# usb_to_uart.net
KiCad netlist of a schematic drawn in Altium Designer
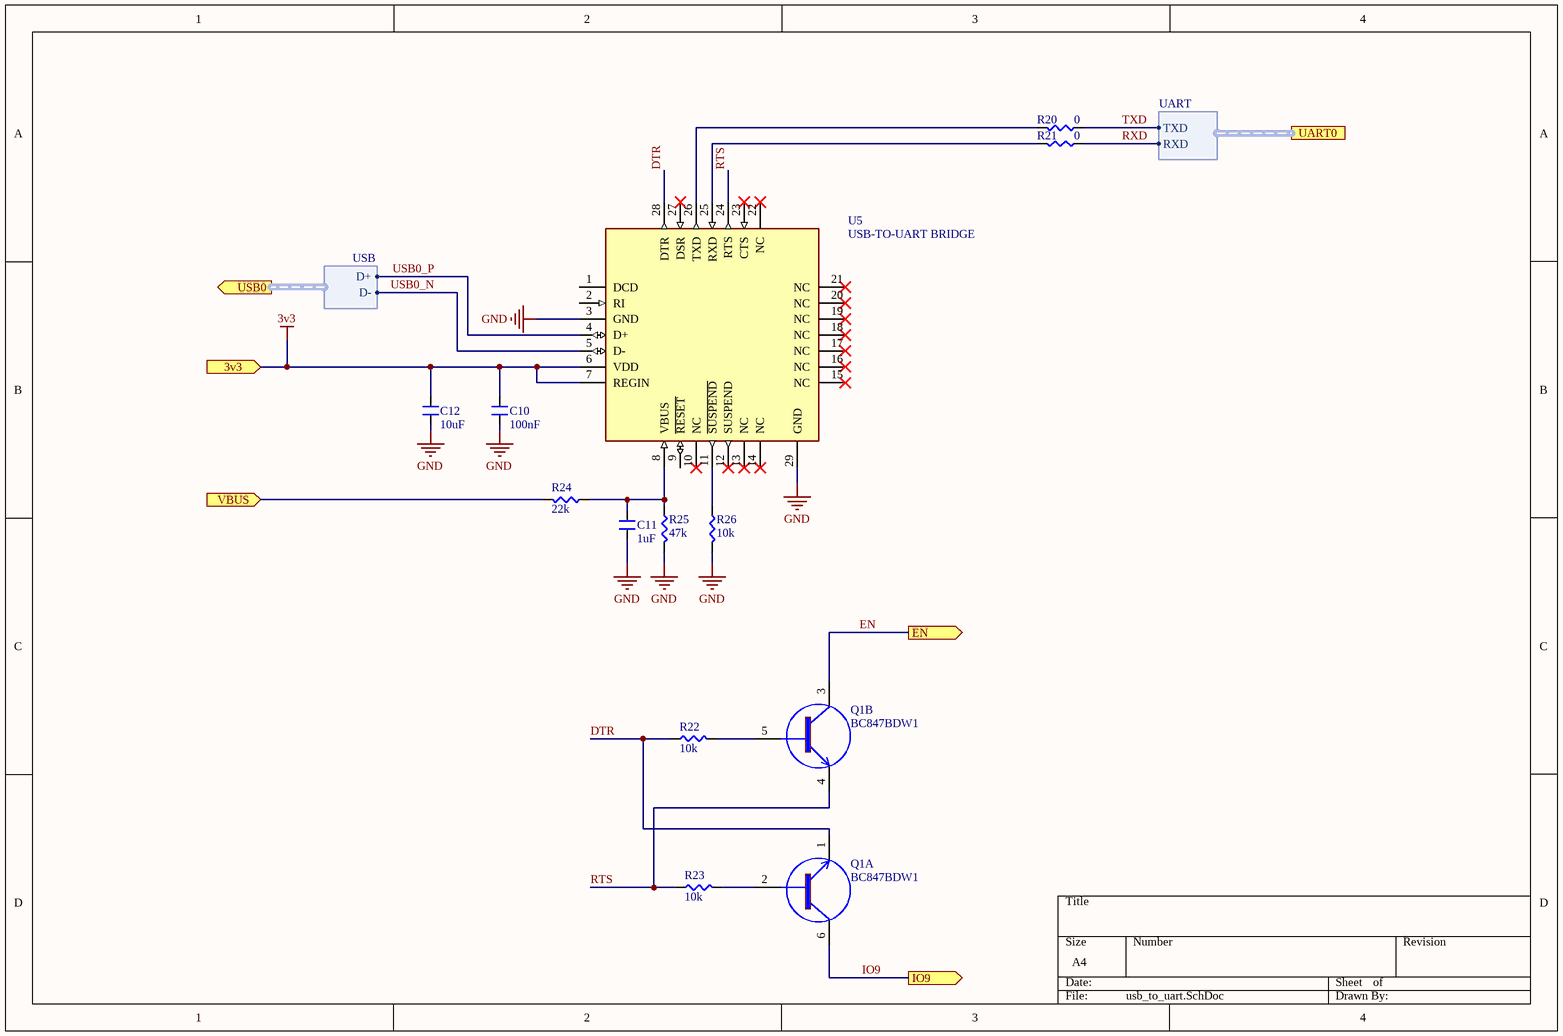
[diagram p0: usb_to_uart.SchDoc]

(export (version "E")
  (design (tool "Eeschema 10.0.6"))
  (components
    (comp (ref "C10")
      (value "100nF")
      (footprint "CAP0603")
      (description "Tolerance ±10%\nRated Voltage 50Vdc\nTemperature 0±30ppm/℃")
      (fields (field (name "PART NUMBER") "GCM188R71H104KA57J") (field (name "TOLERANCE") "10%"))
      (libsource (lib "Lib_Kam") (part "Capacitor"))
    )
    (comp (ref "C11")
      (value "1uF")
      (footprint "CAP1206_38MIL")
      (description "Tolerance ±10%\nRated Voltage 50Vdc\nDielectric:  X7R")
      (fields (field (name "PART NUMBER") "C1206X105K5RECAUTO") (field (name "TOLERANCE") "0,1"))
      (libsource (lib "Lib_Kam") (part "Capacitor"))
    )
    (comp (ref "C12")
      (value "10uF")
      (footprint "CAP1206_63MIL")
      (description "Tolerance ±20%\nVoltage - Rated 50V")
      (fields (field (name "PART NUMBER") "GRT31CR61H106ME01L") (field (name "TOLERANCE") "0,2"))
      (libsource (lib "Lib_Kam") (part "Capacitor"))
    )
    (comp (ref "Q1")
      (value "BC847BDW1")
      (footprint "SOT-363")
      (description "45V 380mW 200@2mA,5V 100mA NPN SOT-363 Bipolar Transistors - BJT ROHS")
      (fields (field (name "MANUFACTURER") "onsemi"))
      (libsource (lib "") (part "NPN_dual_SOT-363_1"))
    )
    (comp (ref "R20")
      (value "0")
      (footprint "RES0603")
      (description "Tolerance ±1%\nPower (Watts) 0.1W, 1/10W\nTemperature Coefficient ±100ppm/°C")
      (fields (field (name "PART NUMBER") "AF0603JR-070RL") (field (name "TOLERANCE") "1%"))
      (libsource (lib "Lib_Kam") (part "Resistor"))
    )
    (comp (ref "R21")
      (value "0")
      (footprint "RES0603")
      (description "Tolerance ±1%\nPower (Watts) 0.1W, 1/10W\nTemperature Coefficient ±100ppm/°C")
      (fields (field (name "PART NUMBER") "AF0603JR-070RL") (field (name "TOLERANCE") "1%"))
      (libsource (lib "Lib_Kam") (part "Resistor"))
    )
    (comp (ref "R22")
      (value "10k")
      (footprint "RES0603")
      (description "Tolerance ±1%\nPower (Watts) 0.1W, 1/10W\nTemperature Coefficient ±100ppm/°C")
      (fields (field (name "PART NUMBER") "CR0603-FX-1002ELF") (field (name "TOLERANCE") "1%"))
      (libsource (lib "Lib_Kam") (part "Resistor"))
    )
    (comp (ref "R23")
      (value "10k")
      (footprint "RES0603")
      (description "Tolerance ±1%\nPower (Watts) 0.1W, 1/10W\nTemperature Coefficient ±100ppm/°C")
      (fields (field (name "PART NUMBER") "CR0603-FX-1002ELF") (field (name "TOLERANCE") "1%"))
      (libsource (lib "Lib_Kam") (part "Resistor"))
    )
    (comp (ref "R24")
      (value "22k")
      (footprint "RES0603")
      (description "Tolerance ±1%\nPower (Watts) 0.1W, 1/10W\nTemperature Coefficient ±100ppm/°C")
      (fields (field (name "PART NUMBER") "CR0603-FX-2202ELF") (field (name "TOLERANCE") "1%"))
      (libsource (lib "Lib_Kam") (part "Resistor"))
    )
    (comp (ref "R25")
      (value "47k")
      (footprint "RES0603")
      (description "Tolerance ±1%\nPower (Watts) 0.1W, 1/10W\nTemperature Coefficient ±100ppm/°C")
      (fields (field (name "PART NUMBER") "ERJ-3EKF4702V") (field (name "TOLERANCE") "1%"))
      (libsource (lib "Lib_Kam") (part "Resistor"))
    )
    (comp (ref "R26")
      (value "10k")
      (footprint "RES0603")
      (description "Tolerance ±1%\nPower (Watts) 0.1W, 1/10W\nTemperature Coefficient ±100ppm/°C")
      (fields (field (name "PART NUMBER") "CR0603-FX-1002ELF") (field (name "TOLERANCE") "1%"))
      (libsource (lib "Lib_Kam") (part "Resistor"))
    )
    (comp (ref "U5")
      (value "USB-TO-UART BRIDGE")
      (footprint "QFN50P480X480X80_HS-29N")
      (description "Voltage - Supply 3V ~ 3.6V\nCurrent - Supply 20mA\nStandards USB 2.0")
      (fields (field (name "MANUFACTURER") "Silicon Lab") (field (name "PART NUMBER") "CP2102"))
      (libsource (lib "Lib_Kam") (part "CP2102/9"))
    )
  )
  (nets
    (net (code "3") (name "/DTR") (class "Default")
      (node (ref "Q1") (pin "1") (pinfunction "E2_1") (pintype "passive"))
      (node (ref "R22") (pin "2") (pintype "passive"))
      (node (ref "U5") (pin "28") (pinfunction "DTR_28") (pintype "output"))
    )
    (net (code "4") (name "/EN") (class "Default")
      (node (ref "Q1") (pin "3") (pinfunction "C2_3") (pintype "passive"))
    )
    (net (code "5") (name "/IO9") (class "Default")
      (node (ref "Q1") (pin "6") (pinfunction "C2_6") (pintype "passive"))
    )
    (net (code "6") (name "/RTS") (class "Default")
      (node (ref "Q1") (pin "4") (pinfunction "E2_4") (pintype "passive"))
      (node (ref "R23") (pin "2") (pintype "passive"))
      (node (ref "U5") (pin "24") (pinfunction "RTS_24") (pintype "output"))
    )
    (net (code "7") (name "/RXD") (class "Default") (node (ref "R21") (pin "2") (pintype "passive")))
    (net (code "8") (name "/TXD") (class "Default") (node (ref "R20") (pin "2") (pintype "passive")))
    (net (code "9") (name "/USB0_N") (class "Default")
      (node (ref "U5") (pin "5") (pinfunction "D-_5") (pintype "bidirectional"))
    )
    (net (code "10") (name "/USB0_P") (class "Default")
      (node (ref "U5") (pin "4") (pinfunction "D+_4") (pintype "bidirectional"))
    )
    (net (code "11") (name "/VBUS") (class "Default") (node (ref "R24") (pin "1") (pintype "passive")))
    (net (code "14") (name "3v3") (class "Default")
      (node (ref "C10") (pin "2") (pinfunction "2_2") (pintype "passive"))
      (node (ref "C12") (pin "2") (pinfunction "2_2") (pintype "passive"))
      (node (ref "U5") (pin "6") (pinfunction "VDD_6") (pintype "power_in"))
      (node (ref "U5") (pin "7") (pinfunction "REGIN_7") (pintype "power_in"))
    )
    (net (code "15") (name "GND") (class "Default")
      (node (ref "C10") (pin "1") (pinfunction "2_1") (pintype "passive"))
      (node (ref "C11") (pin "1") (pinfunction "2_1") (pintype "passive"))
      (node (ref "C12") (pin "1") (pinfunction "2_1") (pintype "passive"))
      (node (ref "R25") (pin "1") (pintype "passive"))
      (node (ref "R26") (pin "1") (pintype "passive"))
      (node (ref "U5") (pin "29") (pinfunction "GND_29") (pintype "power_in"))
      (node (ref "U5") (pin "3") (pinfunction "GND_3") (pintype "power_in"))
    )
    (net (code "16") (name "Net-(Q1A-B2)") (class "Default")
      (node (ref "Q1") (pin "2") (pinfunction "B2_2") (pintype "passive"))
      (node (ref "R23") (pin "1") (pintype "passive"))
    )
    (net (code "17") (name "Net-(Q1B-B2)") (class "Default")
      (node (ref "Q1") (pin "5") (pinfunction "B2_5") (pintype "passive"))
      (node (ref "R22") (pin "1") (pintype "passive"))
    )
    (net (code "18") (name "Net-(U5-RXD)") (class "Default")
      (node (ref "R21") (pin "1") (pintype "passive"))
      (node (ref "U5") (pin "25") (pinfunction "RXD_25") (pintype "input"))
    )
    (net (code "19") (name "Net-(U5-TXD)") (class "Default")
      (node (ref "R20") (pin "1") (pintype "passive"))
      (node (ref "U5") (pin "26") (pinfunction "TXD_26") (pintype "output"))
    )
    (net (code "20") (name "Net-(U5-VBUS)") (class "Default")
      (node (ref "C11") (pin "2") (pinfunction "2_2") (pintype "passive"))
      (node (ref "R24") (pin "2") (pintype "passive"))
      (node (ref "R25") (pin "2") (pintype "passive"))
      (node (ref "U5") (pin "8") (pinfunction "VBUS_8") (pintype "input"))
    )
    (net (code "21") (name "Net-(U5-~{SUSPEND})") (class "Default")
      (node (ref "R26") (pin "2") (pintype "passive"))
      (node (ref "U5") (pin "11") (pinfunction "~{SUSPEND}_11") (pintype "output"))
    )
    (net (code "22") (name "unconnected-(U5-CTS-Pad23)") (class "Default")
      (node (ref "U5") (pin "23") (pinfunction "CTS_23") (pintype "input+no_connect"))
    )
    (net (code "23") (name "unconnected-(U5-DCD-Pad1)") (class "Default")
      (node (ref "U5") (pin "1") (pinfunction "DCD_1") (pintype "passive"))
    )
    (net (code "24") (name "unconnected-(U5-DSR-Pad27)") (class "Default")
      (node (ref "U5") (pin "27") (pinfunction "DSR_27") (pintype "input+no_connect"))
    )
    (net (code "25") (name "unconnected-(U5-NC-Pad10)") (class "Default")
      (node (ref "U5") (pin "10") (pinfunction "NC_10") (pintype "passive+no_connect"))
    )
    (net (code "26") (name "unconnected-(U5-NC-Pad13)") (class "Default")
      (node (ref "U5") (pin "13") (pinfunction "NC_13") (pintype "passive+no_connect"))
    )
    (net (code "27") (name "unconnected-(U5-NC-Pad14)") (class "Default")
      (node (ref "U5") (pin "14") (pinfunction "NC_14") (pintype "passive+no_connect"))
    )
    (net (code "28") (name "unconnected-(U5-NC-Pad15)") (class "Default")
      (node (ref "U5") (pin "15") (pinfunction "NC_15") (pintype "passive+no_connect"))
    )
    (net (code "29") (name "unconnected-(U5-NC-Pad16)") (class "Default")
      (node (ref "U5") (pin "16") (pinfunction "NC_16") (pintype "passive+no_connect"))
    )
    (net (code "30") (name "unconnected-(U5-NC-Pad17)") (class "Default")
      (node (ref "U5") (pin "17") (pinfunction "NC_17") (pintype "passive+no_connect"))
    )
    (net (code "31") (name "unconnected-(U5-NC-Pad18)") (class "Default")
      (node (ref "U5") (pin "18") (pinfunction "NC_18") (pintype "passive+no_connect"))
    )
    (net (code "32") (name "unconnected-(U5-NC-Pad19)") (class "Default")
      (node (ref "U5") (pin "19") (pinfunction "NC_19") (pintype "passive+no_connect"))
    )
    (net (code "33") (name "unconnected-(U5-NC-Pad20)") (class "Default")
      (node (ref "U5") (pin "20") (pinfunction "NC_20") (pintype "passive+no_connect"))
    )
    (net (code "34") (name "unconnected-(U5-NC-Pad21)") (class "Default")
      (node (ref "U5") (pin "21") (pinfunction "NC_21") (pintype "passive+no_connect"))
    )
    (net (code "35") (name "unconnected-(U5-NC-Pad22)") (class "Default")
      (node (ref "U5") (pin "22") (pinfunction "NC_22") (pintype "passive+no_connect"))
    )
    (net (code "36") (name "unconnected-(U5-RI-Pad2)") (class "Default")
      (node (ref "U5") (pin "2") (pinfunction "RI_2") (pintype "input"))
    )
    (net (code "37") (name "unconnected-(U5-SUSPEND-Pad12)") (class "Default")
      (node (ref "U5") (pin "12") (pinfunction "SUSPEND_12") (pintype "output+no_connect"))
    )
    (net (code "38") (name "unconnected-(U5-~{RESET}-Pad9)") (class "Default")
      (node (ref "U5") (pin "9") (pinfunction "~{RESET}_9") (pintype "bidirectional"))
    )
  )
)
